# STM32F103C8T6.net
KiCad netlist of a schematic drawn in EasyEDA
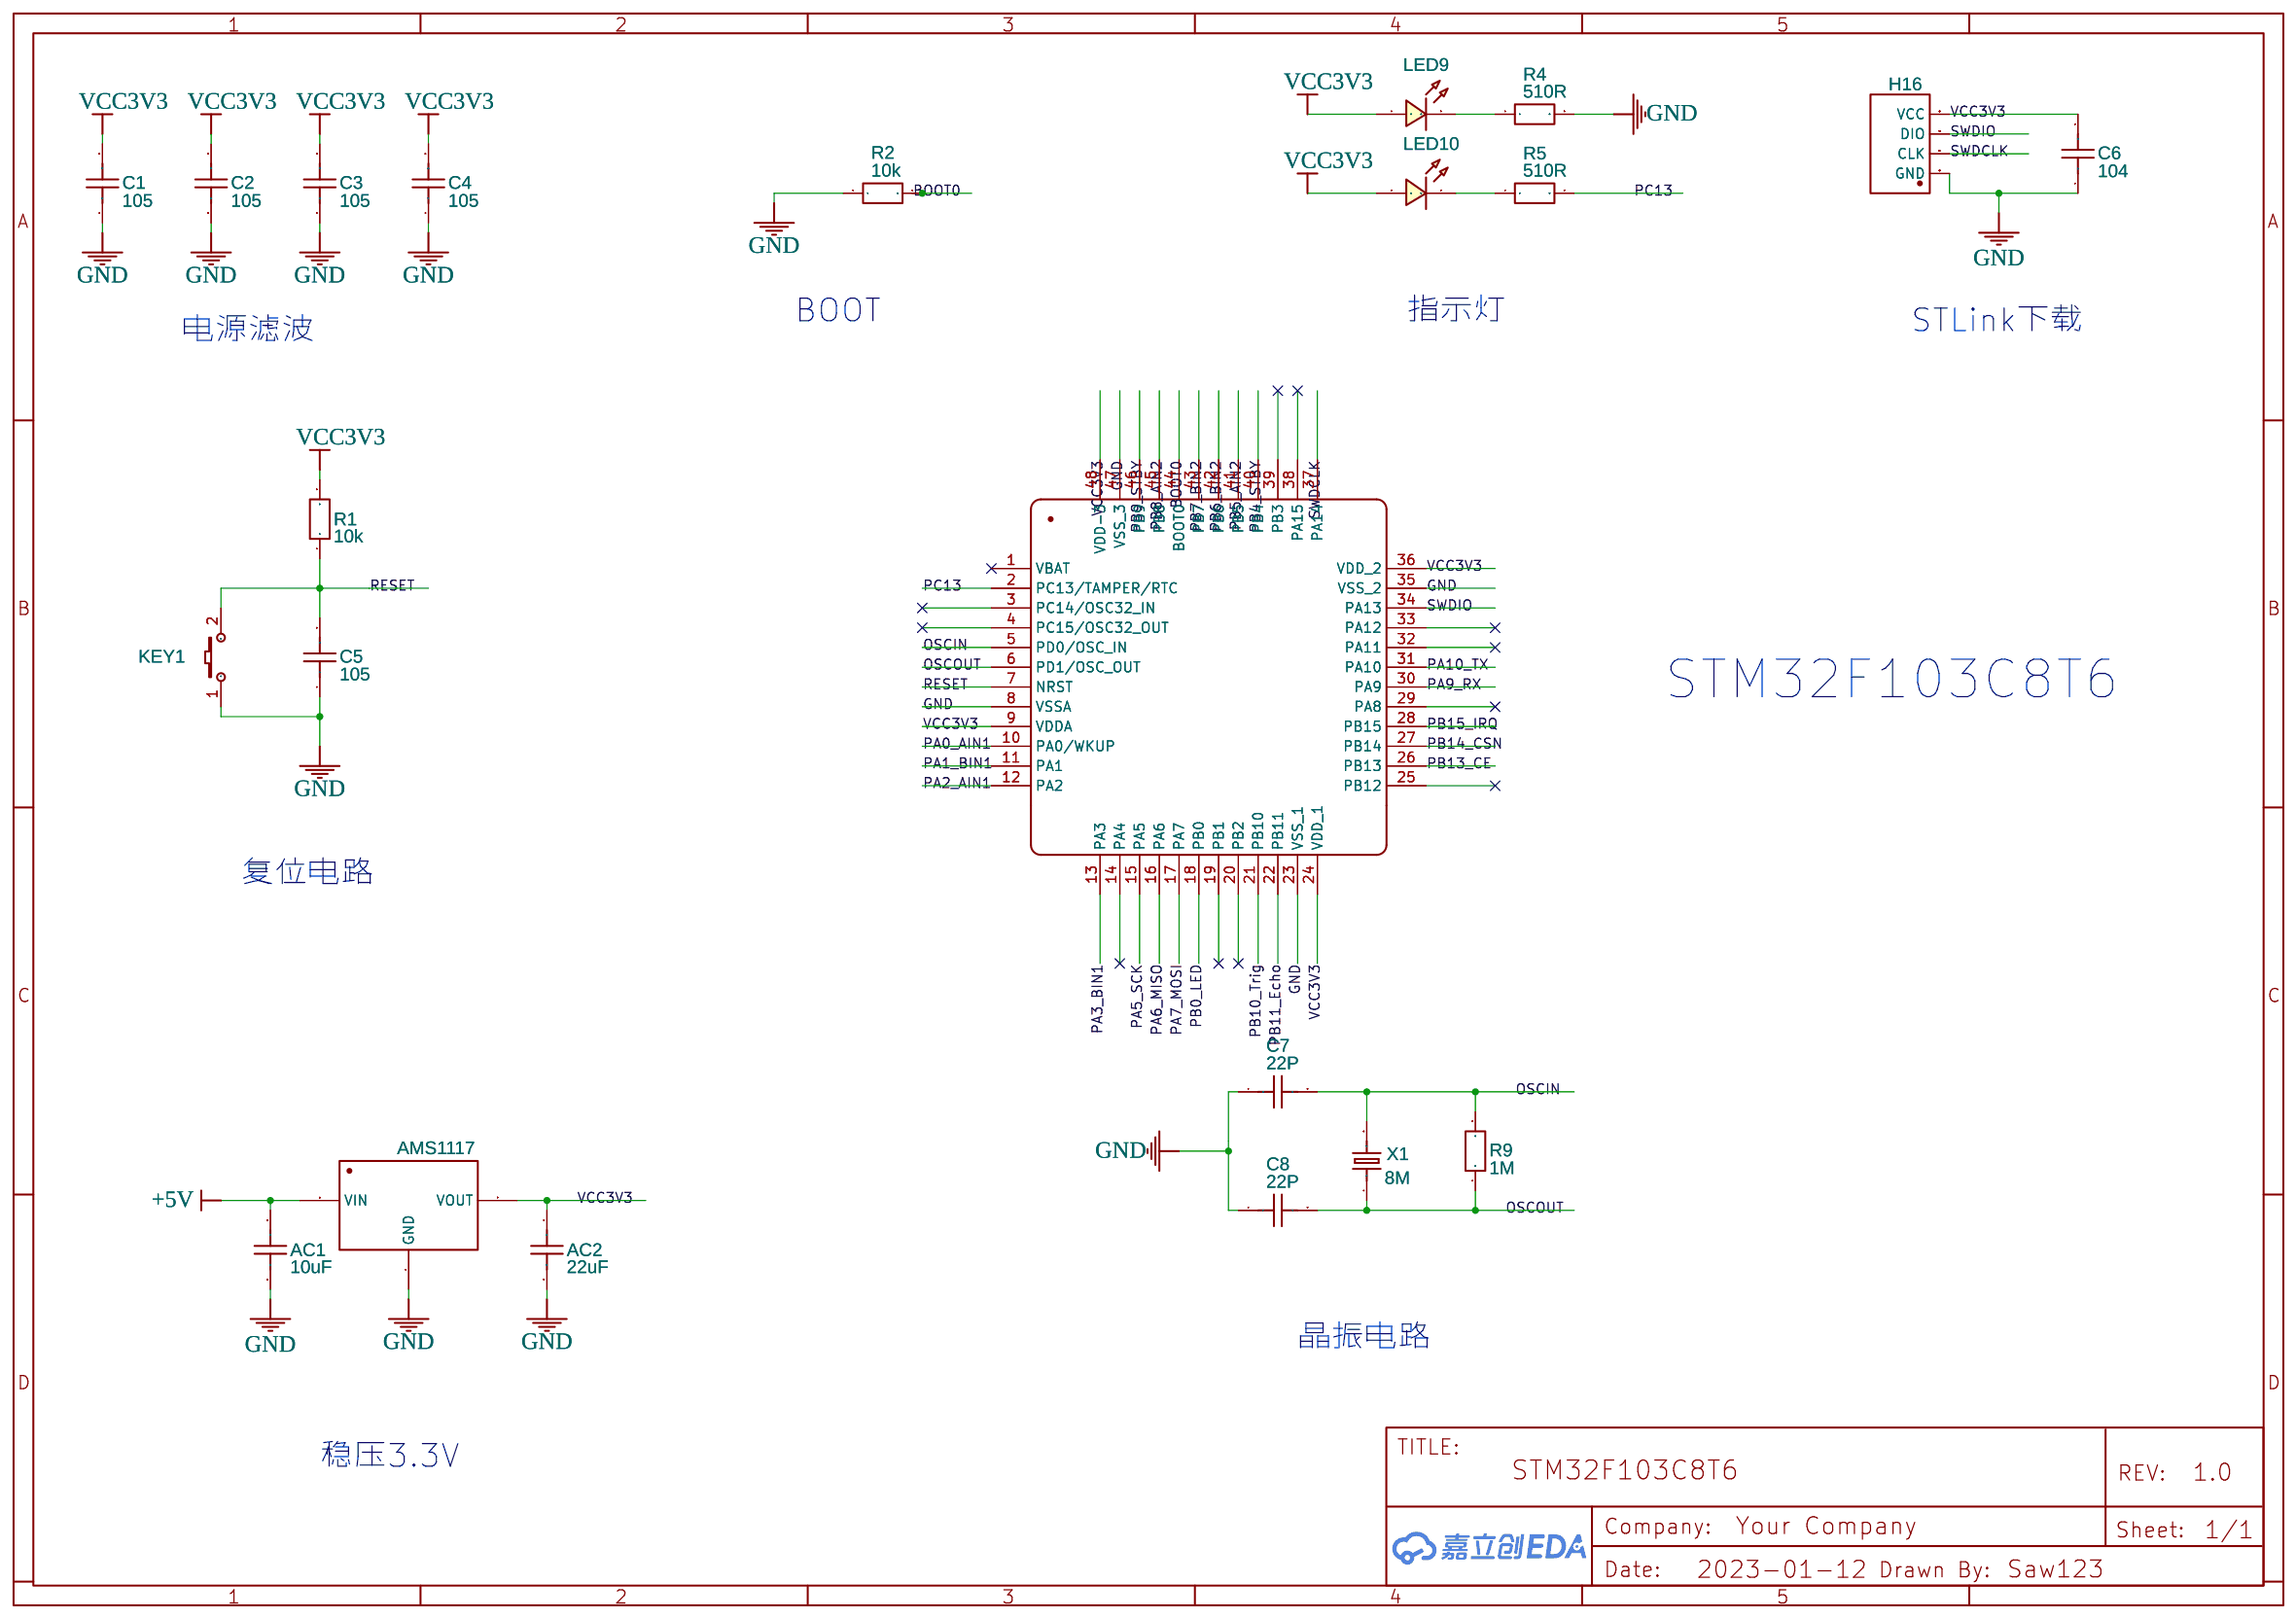
[diagram p0: schematic sheet]

(export (version "E")
  (design (tool "Eeschema 10.0.6"))
  (components
    (comp (ref "AC1") (value "10uF") (libsource (lib "") (part "C_0805_US_2")))
    (comp (ref "AC2") (value "22uF") (libsource (lib "") (part "C_0805_US_2")))
    (comp (ref "AU1") (value "AMS1117") (libsource (lib "") (part "AMS1117")))
    (comp (ref "C1") (value "105") (libsource (lib "") (part "C_0805_US")))
    (comp (ref "C2") (value "105") (libsource (lib "") (part "C_0805_US")))
    (comp (ref "C3") (value "105") (libsource (lib "") (part "C_0805_US")))
    (comp (ref "C4") (value "105") (libsource (lib "") (part "C_0805_US")))
    (comp (ref "C5") (value "105") (libsource (lib "") (part "C_0805_US")))
    (comp (ref "C6") (value "104") (libsource (lib "") (part "C_0805_US")))
    (comp (ref "C7") (value "22P") (libsource (lib "") (part "C_0805_US_1")))
    (comp (ref "C8") (value "22P") (libsource (lib "") (part "C_0805_US_1")))
    (comp (ref "H16") (value "STlink") (libsource (lib "") (part "STlink")))
    (comp (ref "KEY1")
      (value "K2-3.6×6.1_SMD")
      (fields
        (field (name "BOM_Manufacturer Part") "K2-1107ST-A4SW-06")
        (field (name "BOM_Supplier Part") "C118141")
      )
      (libsource (lib "") (part "K2-3.6×6.1_SMD"))
    )
    (comp (ref "LED9")
      (value "LED-0805_R")
      (fields
        (field (name "BOM_Manufacturer Part") "17-21SURC/S530-A3/TR8")
        (field (name "BOM_Supplier Part") "C72037")
      )
      (libsource (lib "") (part "LED-0805_R"))
    )
    (comp (ref "LED10")
      (value "LED-0805_G")
      (fields (field (name "BOM_Manufacturer Part") "NCD0805G1") (field (name "BOM_Supplier Part") "C84260"))
      (libsource (lib "") (part "LED-0805_G"))
    )
    (comp (ref "R1") (value "10k") (libsource (lib "") (part "R_0805_EU_1")))
    (comp (ref "R2") (value "10k") (libsource (lib "") (part "R_0805_EU")))
    (comp (ref "R4") (value "510R") (libsource (lib "") (part "R_0805_EU")))
    (comp (ref "R5") (value "510R") (libsource (lib "") (part "R_0805_EU")))
    (comp (ref "R9") (value "1M") (libsource (lib "") (part "R_0805_EU_1")))
    (comp (ref "U1") (value "STM32F103C8T6") (libsource (lib "") (part "STM32F103C8T6")))
    (comp (ref "X1")
      (value "8M")
      (fields
        (field (name "BOM_Manufacturer Part") "XIHCELNANF-8MHZ")
        (field (name "BOM_Supplier Part") "C295088")
      )
      (libsource (lib "") (part "XIHCELNANF-8MHZ"))
    )
  )
  (nets
    (net (code "1") (name "+5V") (class "Default")
      (node (ref "AC1") (pin "1") (pinfunction "1_1") (pintype "unspecified"))
      (node (ref "AU1") (pin "3") (pinfunction "VIN_3") (pintype "unspecified"))
    )
    (net (code "2") (name "/BOOT0") (class "Default")
      (node (ref "R2") (pin "2") (pinfunction "2_2") (pintype "unspecified"))
      (node (ref "U1") (pin "44") (pinfunction "BOOT0_44") (pintype "unspecified"))
    )
    (net (code "3") (name "/OSCIN") (class "Default")
      (node (ref "C7") (pin "2") (pinfunction "2_2") (pintype "unspecified"))
      (node (ref "R9") (pin "2") (pinfunction "2_2") (pintype "unspecified"))
      (node (ref "U1") (pin "5") (pinfunction "PD0/OSC_IN_5") (pintype "unspecified"))
      (node (ref "X1") (pin "2") (pinfunction "2_2") (pintype "unspecified"))
    )
    (net (code "4") (name "/OSCOUT") (class "Default")
      (node (ref "C8") (pin "2") (pinfunction "2_2") (pintype "unspecified"))
      (node (ref "R9") (pin "1") (pinfunction "1_1") (pintype "unspecified"))
      (node (ref "U1") (pin "6") (pinfunction "PD1/OSC_OUT_6") (pintype "unspecified"))
      (node (ref "X1") (pin "1") (pinfunction "1_1") (pintype "unspecified"))
    )
    (net (code "5") (name "/PA0_AIN1") (class "Default")
      (node (ref "U1") (pin "10") (pinfunction "PA0/WKUP_10") (pintype "unspecified"))
    )
    (net (code "6") (name "/PA1_BIN1") (class "Default")
      (node (ref "U1") (pin "11") (pinfunction "PA1_11") (pintype "unspecified"))
    )
    (net (code "7") (name "/PA2_AIN1") (class "Default")
      (node (ref "U1") (pin "12") (pinfunction "PA2_12") (pintype "unspecified"))
    )
    (net (code "8") (name "/PA3_BIN1") (class "Default")
      (node (ref "U1") (pin "13") (pinfunction "PA3_13") (pintype "unspecified"))
    )
    (net (code "9") (name "/PA5_SCK") (class "Default")
      (node (ref "U1") (pin "15") (pinfunction "PA5_15") (pintype "unspecified"))
    )
    (net (code "10") (name "/PA6_MISO") (class "Default")
      (node (ref "U1") (pin "16") (pinfunction "PA6_16") (pintype "unspecified"))
    )
    (net (code "11") (name "/PA7_MOSI") (class "Default")
      (node (ref "U1") (pin "17") (pinfunction "PA7_17") (pintype "unspecified"))
    )
    (net (code "12") (name "/PA9_RX") (class "Default")
      (node (ref "U1") (pin "30") (pinfunction "PA9_30") (pintype "unspecified"))
    )
    (net (code "13") (name "/PA10_TX") (class "Default")
      (node (ref "U1") (pin "31") (pinfunction "PA10_31") (pintype "unspecified"))
    )
    (net (code "14") (name "/PB0_LED") (class "Default")
      (node (ref "U1") (pin "18") (pinfunction "PB0_18") (pintype "unspecified"))
    )
    (net (code "15") (name "/PB4_STBY") (class "Default")
      (node (ref "U1") (pin "40") (pinfunction "PB4_40") (pintype "unspecified"))
    )
    (net (code "16") (name "/PB5_AIN2") (class "Default")
      (node (ref "U1") (pin "41") (pinfunction "PB5_41") (pintype "unspecified"))
    )
    (net (code "17") (name "/PB6_BIN2") (class "Default")
      (node (ref "U1") (pin "42") (pinfunction "PB6_42") (pintype "unspecified"))
    )
    (net (code "18") (name "/PB7_BIN2") (class "Default")
      (node (ref "U1") (pin "43") (pinfunction "PB7_43") (pintype "unspecified"))
    )
    (net (code "19") (name "/PB8_AIN2") (class "Default")
      (node (ref "U1") (pin "45") (pinfunction "PB8_45") (pintype "unspecified"))
    )
    (net (code "20") (name "/PB9_STBY") (class "Default")
      (node (ref "U1") (pin "46") (pinfunction "PB9_46") (pintype "unspecified"))
    )
    (net (code "21") (name "/PB10_Trig") (class "Default")
      (node (ref "U1") (pin "21") (pinfunction "PB10_21") (pintype "unspecified"))
    )
    (net (code "22") (name "/PB11_Echo") (class "Default")
      (node (ref "U1") (pin "22") (pinfunction "PB11_22") (pintype "unspecified"))
    )
    (net (code "23") (name "/PB13_CE") (class "Default")
      (node (ref "U1") (pin "26") (pinfunction "PB13_26") (pintype "unspecified"))
    )
    (net (code "24") (name "/PB14_CSN") (class "Default")
      (node (ref "U1") (pin "27") (pinfunction "PB14_27") (pintype "unspecified"))
    )
    (net (code "25") (name "/PB15_IRQ") (class "Default")
      (node (ref "U1") (pin "28") (pinfunction "PB15_28") (pintype "unspecified"))
    )
    (net (code "26") (name "/PC13") (class "Default")
      (node (ref "R5") (pin "2") (pinfunction "2_2") (pintype "unspecified"))
      (node (ref "U1") (pin "2") (pinfunction "PC13/TAMPER/RTC_2") (pintype "unspecified"))
    )
    (net (code "27") (name "/RESET") (class "Default")
      (node (ref "C5") (pin "2") (pinfunction "2_2") (pintype "unspecified"))
      (node (ref "KEY1") (pin "2") (pinfunction "2_2") (pintype "unspecified"))
      (node (ref "R1") (pin "1") (pinfunction "1_1") (pintype "unspecified"))
      (node (ref "U1") (pin "7") (pinfunction "NRST_7") (pintype "unspecified"))
    )
    (net (code "28") (name "/SWDCLK") (class "Default")
      (node (ref "H16") (pin "CLK") (pinfunction "CLK_CLK") (pintype "unspecified"))
      (node (ref "U1") (pin "37") (pinfunction "PA14_37") (pintype "unspecified"))
    )
    (net (code "29") (name "/SWDIO") (class "Default")
      (node (ref "H16") (pin "DIO") (pinfunction "DIO_DIO") (pintype "unspecified"))
      (node (ref "U1") (pin "34") (pinfunction "PA13_34") (pintype "unspecified"))
    )
    (net (code "30") (name "GND") (class "Default")
      (node (ref "AC1") (pin "2") (pinfunction "2_2") (pintype "unspecified"))
      (node (ref "AC2") (pin "2") (pinfunction "2_2") (pintype "unspecified"))
      (node (ref "AU1") (pin "1") (pinfunction "GND_1") (pintype "unspecified"))
      (node (ref "C1") (pin "1") (pinfunction "1_1") (pintype "unspecified"))
      (node (ref "C2") (pin "1") (pinfunction "1_1") (pintype "unspecified"))
      (node (ref "C3") (pin "1") (pinfunction "1_1") (pintype "unspecified"))
      (node (ref "C4") (pin "1") (pinfunction "1_1") (pintype "unspecified"))
      (node (ref "C5") (pin "1") (pinfunction "1_1") (pintype "unspecified"))
      (node (ref "C6") (pin "1") (pinfunction "1_1") (pintype "unspecified"))
      (node (ref "C7") (pin "1") (pinfunction "1_1") (pintype "unspecified"))
      (node (ref "C8") (pin "1") (pinfunction "1_1") (pintype "unspecified"))
      (node (ref "H16") (pin "GND") (pinfunction "GND_GND") (pintype "unspecified"))
      (node (ref "KEY1") (pin "1") (pinfunction "1_1") (pintype "unspecified"))
      (node (ref "R2") (pin "1") (pinfunction "1_1") (pintype "unspecified"))
      (node (ref "R4") (pin "2") (pinfunction "2_2") (pintype "unspecified"))
      (node (ref "U1") (pin "23") (pinfunction "VSS_1_23") (pintype "unspecified"))
      (node (ref "U1") (pin "35") (pinfunction "VSS_2_35") (pintype "unspecified"))
      (node (ref "U1") (pin "47") (pinfunction "VSS_3_47") (pintype "unspecified"))
      (node (ref "U1") (pin "8") (pinfunction "VSSA_8") (pintype "unspecified"))
    )
    (net (code "31") (name "Net-(LED9-Pad2)") (class "Default")
      (node (ref "LED9") (pin "2") (pinfunction "2_2") (pintype "unspecified"))
      (node (ref "R4") (pin "1") (pinfunction "1_1") (pintype "unspecified"))
    )
    (net (code "32") (name "Net-(LED10-Pad2)") (class "Default")
      (node (ref "LED10") (pin "2") (pinfunction "2_2") (pintype "unspecified"))
      (node (ref "R5") (pin "1") (pinfunction "1_1") (pintype "unspecified"))
    )
    (net (code "33") (name "VCC3V3") (class "Default")
      (node (ref "AC2") (pin "1") (pinfunction "1_1") (pintype "unspecified"))
      (node (ref "AU1") (pin "2") (pinfunction "VOUT_2") (pintype "unspecified"))
      (node (ref "C1") (pin "2") (pinfunction "2_2") (pintype "unspecified"))
      (node (ref "C2") (pin "2") (pinfunction "2_2") (pintype "unspecified"))
      (node (ref "C3") (pin "2") (pinfunction "2_2") (pintype "unspecified"))
      (node (ref "C4") (pin "2") (pinfunction "2_2") (pintype "unspecified"))
      (node (ref "C6") (pin "2") (pinfunction "2_2") (pintype "unspecified"))
      (node (ref "H16") (pin "VCC") (pinfunction "VCC_VCC") (pintype "unspecified"))
      (node (ref "LED10") (pin "1") (pinfunction "1_1") (pintype "unspecified"))
      (node (ref "LED9") (pin "1") (pinfunction "1_1") (pintype "unspecified"))
      (node (ref "R1") (pin "2") (pinfunction "2_2") (pintype "unspecified"))
      (node (ref "U1") (pin "24") (pinfunction "VDD_1_24") (pintype "unspecified"))
      (node (ref "U1") (pin "36") (pinfunction "VDD_2_36") (pintype "unspecified"))
      (node (ref "U1") (pin "48") (pinfunction "VDD-3_48") (pintype "unspecified"))
      (node (ref "U1") (pin "9") (pinfunction "VDDA_9") (pintype "unspecified"))
    )
    (net (code "34") (name "unconnected-(U1-PA4-Pad14)") (class "Default")
      (node (ref "U1") (pin "14") (pinfunction "PA4_14") (pintype "unspecified+no_connect"))
    )
    (net (code "35") (name "unconnected-(U1-PA8-Pad29)") (class "Default")
      (node (ref "U1") (pin "29") (pinfunction "PA8_29") (pintype "unspecified+no_connect"))
    )
    (net (code "36") (name "unconnected-(U1-PA11-Pad32)") (class "Default")
      (node (ref "U1") (pin "32") (pinfunction "PA11_32") (pintype "unspecified+no_connect"))
    )
    (net (code "37") (name "unconnected-(U1-PA12-Pad33)") (class "Default")
      (node (ref "U1") (pin "33") (pinfunction "PA12_33") (pintype "unspecified+no_connect"))
    )
    (net (code "38") (name "unconnected-(U1-PA15-Pad38)") (class "Default")
      (node (ref "U1") (pin "38") (pinfunction "PA15_38") (pintype "unspecified+no_connect"))
    )
    (net (code "39") (name "unconnected-(U1-PB1-Pad19)") (class "Default")
      (node (ref "U1") (pin "19") (pinfunction "PB1_19") (pintype "unspecified+no_connect"))
    )
    (net (code "40") (name "unconnected-(U1-PB2-Pad20)") (class "Default")
      (node (ref "U1") (pin "20") (pinfunction "PB2_20") (pintype "unspecified+no_connect"))
    )
    (net (code "41") (name "unconnected-(U1-PB3-Pad39)") (class "Default")
      (node (ref "U1") (pin "39") (pinfunction "PB3_39") (pintype "unspecified+no_connect"))
    )
    (net (code "42") (name "unconnected-(U1-PB12-Pad25)") (class "Default")
      (node (ref "U1") (pin "25") (pinfunction "PB12_25") (pintype "unspecified+no_connect"))
    )
    (net (code "43") (name "unconnected-(U1-PC14{slash}OSC32_IN-Pad3)") (class "Default")
      (node (ref "U1") (pin "3") (pinfunction "PC14/OSC32_IN_3") (pintype "unspecified+no_connect"))
    )
    (net (code "44") (name "unconnected-(U1-PC15{slash}OSC32_OUT-Pad4)") (class "Default")
      (node (ref "U1") (pin "4") (pinfunction "PC15/OSC32_OUT_4") (pintype "unspecified+no_connect"))
    )
    (net (code "45") (name "unconnected-(U1-VBAT-Pad1)") (class "Default")
      (node (ref "U1") (pin "1") (pinfunction "VBAT_1") (pintype "unspecified+no_connect"))
    )
  )
)
